# Pawn.net
KiCad netlist of a schematic drawn in EAGLE
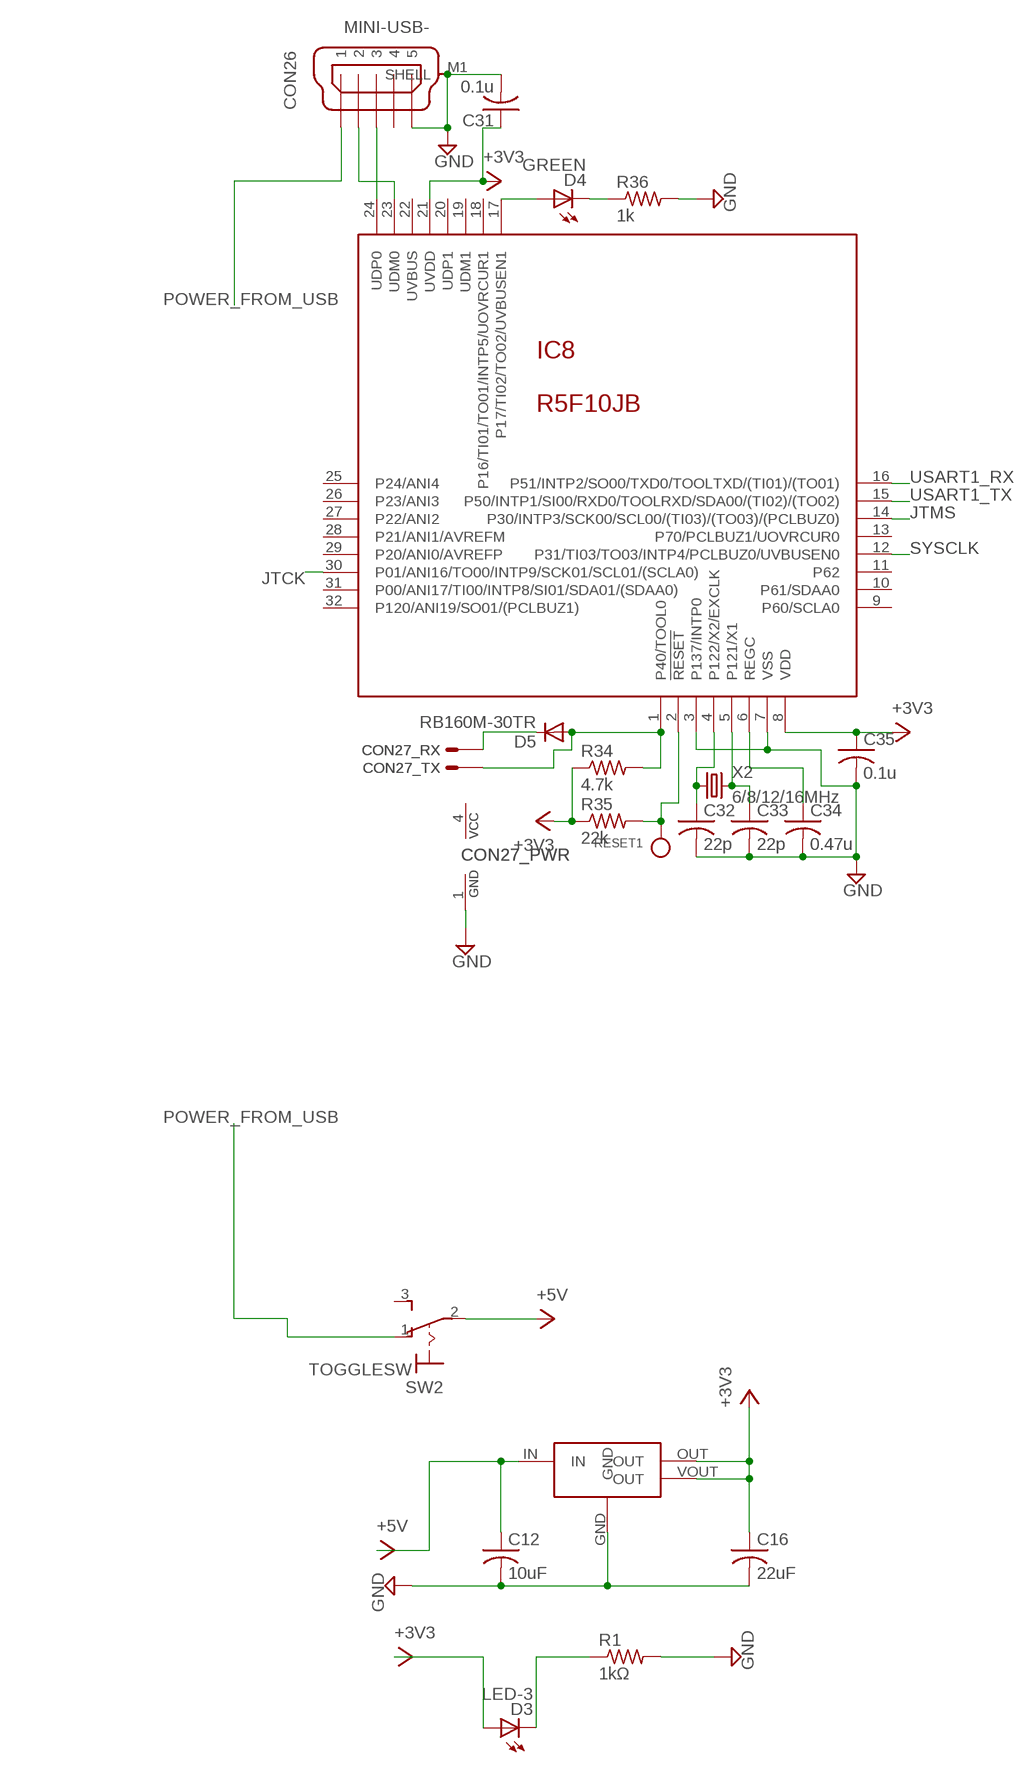
[diagram p0: schematic, sheet 1, part 1 of 2]
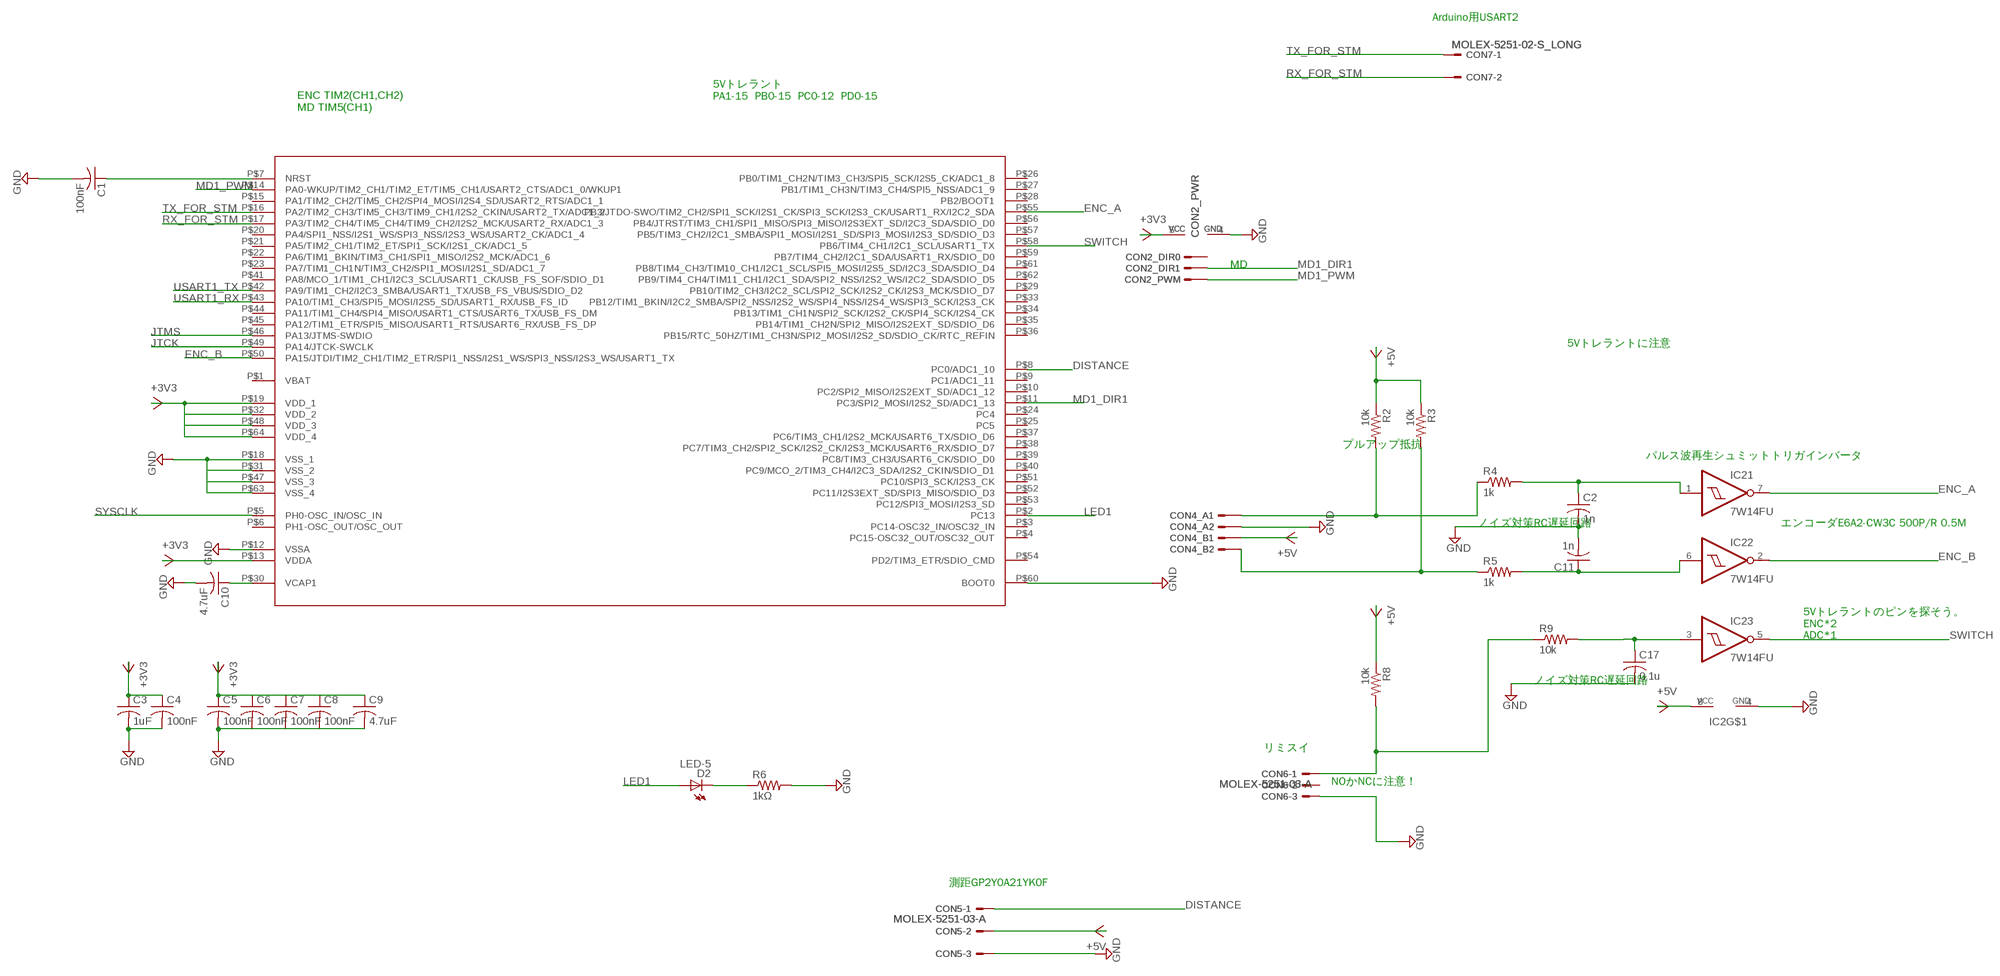
[diagram p1: schematic, sheet 1, part 2 of 2]

(export (version "E")
  (design (tool "Eeschema 10.0.6"))
  (components
    (comp (ref "C1")
      (value "100nF")
      (footprint "eagle-import:2012-C")
      (libsource (lib "eagle-import") (part "C-2012"))
    )
    (comp (ref "C2")
      (value "1n")
      (footprint "eagle-import:2012-C")
      (libsource (lib "eagle-import") (part "C-2012"))
    )
    (comp (ref "C3")
      (value "1uF")
      (footprint "eagle-import:2012-C")
      (libsource (lib "eagle-import") (part "C-2012"))
    )
    (comp (ref "C4")
      (value "100nF")
      (footprint "eagle-import:2012-C")
      (libsource (lib "eagle-import") (part "C-2012"))
    )
    (comp (ref "C5")
      (value "100nF")
      (footprint "eagle-import:2012-C")
      (libsource (lib "eagle-import") (part "C-2012"))
    )
    (comp (ref "C6")
      (value "100nF")
      (footprint "eagle-import:2012-C")
      (libsource (lib "eagle-import") (part "C-2012"))
    )
    (comp (ref "C7")
      (value "100nF")
      (footprint "eagle-import:2012-C")
      (libsource (lib "eagle-import") (part "C-2012"))
    )
    (comp (ref "C8")
      (value "100nF")
      (footprint "eagle-import:2012-C")
      (libsource (lib "eagle-import") (part "C-2012"))
    )
    (comp (ref "C9")
      (value "4.7uF")
      (footprint "eagle-import:2012-C")
      (libsource (lib "eagle-import") (part "C-2012"))
    )
    (comp (ref "C10")
      (value "4.7uF")
      (footprint "eagle-import:2012-C")
      (libsource (lib "eagle-import") (part "C-2012"))
    )
    (comp (ref "C11")
      (value "1n")
      (footprint "eagle-import:2012-C")
      (libsource (lib "eagle-import") (part "C-2012"))
    )
    (comp (ref "C12")
      (value "10uF")
      (footprint "eagle-import:2012-C")
      (libsource (lib "eagle-import") (part "C-2012"))
    )
    (comp (ref "C16")
      (value "22uF")
      (footprint "eagle-import:2012-C")
      (libsource (lib "eagle-import") (part "C-2012"))
    )
    (comp (ref "C17")
      (value "0.1u")
      (footprint "eagle-import:2012-C")
      (libsource (lib "eagle-import") (part "C-2012"))
    )
    (comp (ref "C31")
      (value "0.1u")
      (footprint "eagle-import:2012-C")
      (libsource (lib "eagle-import") (part "C-2012"))
    )
    (comp (ref "C32")
      (value "22p")
      (footprint "eagle-import:1608")
      (libsource (lib "eagle-import") (part "C-1608"))
    )
    (comp (ref "C33")
      (value "22p")
      (footprint "eagle-import:1608")
      (libsource (lib "eagle-import") (part "C-1608"))
    )
    (comp (ref "C34")
      (value "0.47u")
      (footprint "eagle-import:2012-C")
      (libsource (lib "eagle-import") (part "C-2012"))
    )
    (comp (ref "C35")
      (value "0.1u")
      (footprint "eagle-import:2012-C")
      (libsource (lib "eagle-import") (part "C-2012"))
    )
    (comp (ref "CON2")
      (value "MTDRV-A")
      (footprint "eagle-import:5251-05-A")
      (libsource (lib "eagle-import") (part "MTDRV-A"))
    )
    (comp (ref "CON4")
      (value "D-3500-4")
      (footprint "eagle-import:D3500D-4-HORIZONTAL")
      (libsource (lib "eagle-import") (part "D-3500-4"))
    )
    (comp (ref "CON5")
      (value "MOLEX-5251-03-A")
      (footprint "eagle-import:5251-03-A")
      (libsource (lib "eagle-import") (part "MOLEX-5251-03-A"))
    )
    (comp (ref "CON6")
      (value "MOLEX-5251-03-A")
      (footprint "eagle-import:5251-03-A")
      (libsource (lib "eagle-import") (part "MOLEX-5251-03-A"))
    )
    (comp (ref "CON7")
      (value "MOLEX-5251-02-S_LONG")
      (footprint "eagle-import:5251-02-S_LONG")
      (libsource (lib "eagle-import") (part "MOLEX-5251-02-S_LONG"))
    )
    (comp (ref "CON26")
      (value "MINI-USB-")
      (footprint "eagle-import:UX60A-MB-5ST")
      (libsource (lib "eagle-import") (part "MINI-USB-"))
    )
    (comp (ref "CON27")
      (value "UART-S")
      (footprint "eagle-import:IL-G-04-S")
      (libsource (lib "eagle-import") (part "UART-S"))
    )
    (comp (ref "D2")
      (value "LED-5")
      (footprint "eagle-import:LED5")
      (libsource (lib "eagle-import") (part "LED-5"))
    )
    (comp (ref "D3")
      (value "LED-3")
      (footprint "eagle-import:LED3")
      (libsource (lib "eagle-import") (part "LED-3"))
    )
    (comp (ref "D4")
      (value "GREEN")
      (footprint "eagle-import:LED3")
      (libsource (lib "eagle-import") (part "LED-3"))
    )
    (comp (ref "D5")
      (value "RB160M-30TR")
      (footprint "eagle-import:D3216")
      (libsource (lib "eagle-import") (part "DIODE-SMD3216"))
    )
    (comp (ref "IC1")
      (value "AZ1086H-3.3")
      (footprint "eagle-import:SOT223")
      (libsource (lib "eagle-import") (part "AZ1086?-H3.3"))
    )
    (comp (ref "IC2")
      (value "7W14FU")
      (footprint "eagle-import:MSOP8")
      (libsource (lib "eagle-import") (part "7W14FU"))
    )
    (comp (ref "IC8")
      (value "R5F10JB")
      (footprint "eagle-import:TQFP32-08")
      (libsource (lib "eagle-import") (part "R5F10JB"))
    )
    (comp (ref "R1")
      (value "1kΩ")
      (footprint "eagle-import:2012-R")
      (libsource (lib "eagle-import") (part "R-2012"))
    )
    (comp (ref "R2")
      (value "10k")
      (footprint "eagle-import:2012-R")
      (libsource (lib "eagle-import") (part "R-2012"))
    )
    (comp (ref "R3")
      (value "10k")
      (footprint "eagle-import:2012-R")
      (libsource (lib "eagle-import") (part "R-2012"))
    )
    (comp (ref "R4")
      (value "1k")
      (footprint "eagle-import:2012-R")
      (libsource (lib "eagle-import") (part "R-2012"))
    )
    (comp (ref "R5")
      (value "1k")
      (footprint "eagle-import:2012-R")
      (libsource (lib "eagle-import") (part "R-2012"))
    )
    (comp (ref "R6")
      (value "1kΩ")
      (footprint "eagle-import:2012-R")
      (libsource (lib "eagle-import") (part "R-2012"))
    )
    (comp (ref "R8")
      (value "10k")
      (footprint "eagle-import:2012-R")
      (libsource (lib "eagle-import") (part "R-2012"))
    )
    (comp (ref "R9")
      (value "10k")
      (footprint "eagle-import:2012-R")
      (libsource (lib "eagle-import") (part "R-2012"))
    )
    (comp (ref "R34")
      (value "4.7k")
      (footprint "eagle-import:2012-R")
      (libsource (lib "eagle-import") (part "R-2012"))
    )
    (comp (ref "R35")
      (value "22k")
      (footprint "eagle-import:2012-R")
      (libsource (lib "eagle-import") (part "R-2012"))
    )
    (comp (ref "R36")
      (value "1k")
      (footprint "eagle-import:2012-R")
      (libsource (lib "eagle-import") (part "R-2012"))
    )
    (comp (ref "RESET1")
      (value "CHECK_PIN")
      (footprint "eagle-import:SLC-22-G")
      (libsource (lib "eagle-import") (part "CHECK_PIN"))
    )
    (comp (ref "SW2")
      (value "TOGGLESW")
      (footprint "eagle-import:TOGGLESW")
      (libsource (lib "eagle-import") (part "TOGGLESW"))
    )
    (comp (ref "U$1")
      (value "STM32F411RET6")
      (footprint "eagle-import:ET-PCB-LQFP64")
      (libsource (lib "eagle-import") (part "STM32F411RET6"))
    )
    (comp (ref "X2")
      (value "6/8/12/16MHz")
      (footprint "eagle-import:HC49_S")
      (libsource (lib "eagle-import") (part "CRYSTALHC49S"))
    )
  )
  (nets
    (net (code "1") (name "+3V3") (class "Default")
      (node (ref "C16") (pin "1") (pinfunction "1_1") (pintype "passive"))
      (node (ref "C3") (pin "1") (pinfunction "1_1") (pintype "passive"))
      (node (ref "C31") (pin "1") (pinfunction "1_1") (pintype "passive"))
      (node (ref "C35") (pin "1") (pinfunction "1_1") (pintype "passive"))
      (node (ref "C4") (pin "1") (pinfunction "1_1") (pintype "passive"))
      (node (ref "C5") (pin "1") (pinfunction "1_1") (pintype "passive"))
      (node (ref "C6") (pin "1") (pinfunction "1_1") (pintype "passive"))
      (node (ref "C7") (pin "1") (pinfunction "1_1") (pintype "passive"))
      (node (ref "C8") (pin "1") (pinfunction "1_1") (pintype "passive"))
      (node (ref "C9") (pin "1") (pinfunction "1_1") (pintype "passive"))
      (node (ref "CON2") (pin "5") (pinfunction "VCC_5") (pintype "power_in"))
      (node (ref "D3") (pin "A") (pinfunction "A_A") (pintype "passive"))
      (node (ref "IC1") (pin "OUT") (pinfunction "OUT_OUT") (pintype "power_in"))
      (node (ref "IC1") (pin "VOUT") (pinfunction "OUT_VOUT") (pintype "power_in"))
      (node (ref "IC8") (pin "21") (pinfunction "UVDD_21") (pintype "bidirectional"))
      (node (ref "IC8") (pin "8") (pinfunction "VDD_8") (pintype "bidirectional"))
      (node (ref "R34") (pin "1") (pinfunction "1_1") (pintype "passive"))
      (node (ref "R35") (pin "1") (pinfunction "1_1") (pintype "passive"))
      (node (ref "U$1") (pin "P$13") (pinfunction "VDDA_P$13") (pintype "bidirectional"))
      (node (ref "U$1") (pin "P$19") (pinfunction "VDD_1_P$19") (pintype "bidirectional"))
      (node (ref "U$1") (pin "P$32") (pinfunction "VDD_2_P$32") (pintype "bidirectional"))
      (node (ref "U$1") (pin "P$48") (pinfunction "VDD_3_P$48") (pintype "bidirectional"))
      (node (ref "U$1") (pin "P$64") (pinfunction "VDD_4_P$64") (pintype "bidirectional"))
    )
    (net (code "2") (name "+5V") (class "Default")
      (node (ref "C12") (pin "1") (pinfunction "1_1") (pintype "passive"))
      (node (ref "CON4") (pin "B1") (pinfunction "S_B1") (pintype "passive"))
      (node (ref "CON5") (pin "2") (pinfunction "S_2") (pintype "passive"))
      (node (ref "IC1") (pin "IN") (pinfunction "IN_IN") (pintype "power_in"))
      (node (ref "IC2") (pin "8") (pinfunction "VCC_8") (pintype "power_in"))
      (node (ref "R2") (pin "1") (pinfunction "1_1") (pintype "passive"))
      (node (ref "R3") (pin "1") (pinfunction "1_1") (pintype "passive"))
      (node (ref "R8") (pin "1") (pinfunction "1_1") (pintype "passive"))
      (node (ref "SW2") (pin "2") (pinfunction "P_2") (pintype "passive"))
    )
    (net (code "3") (name "/DISTANCE") (class "Default")
      (node (ref "CON5") (pin "1") (pinfunction "S_1") (pintype "passive"))
      (node (ref "U$1") (pin "P$8") (pinfunction "PC0/ADC1_10_P$8") (pintype "bidirectional"))
    )
    (net (code "4") (name "/ENC_A") (class "Default")
      (node (ref "IC2") (pin "7") (pinfunction "Y_7") (pintype "output"))
      (node (ref "U$1") (pin "P$55") (pinfunction "PB3/JTDO-SWO/TIM2_CH2/SPI1_SCK/I2S1_CK/SPI3_SCK/I2S3_CK/USART1_RX/I2C2_SDA_P$55") (pintype "bidirectional"))
    )
    (net (code "5") (name "/ENC_B") (class "Default")
      (node (ref "IC2") (pin "2") (pinfunction "Y_2") (pintype "output"))
      (node (ref "U$1") (pin "P$50") (pinfunction "PA15/JTDI/TIM2_CH1/TIM2_ETR/SPI1_NSS/I2S1_WS/SPI3_NSS/I2S3_WS/USART1_TX_P$50") (pintype "bidirectional"))
    )
    (net (code "6") (name "/JTCK") (class "Default")
      (node (ref "IC8") (pin "30") (pinfunction "P01/ANI16/TO00/INTP9/SCK01/SCL01/(SCLA0)_30") (pintype "bidirectional"))
      (node (ref "U$1") (pin "P$49") (pinfunction "PA14/JTCK-SWCLK_P$49") (pintype "bidirectional"))
    )
    (net (code "7") (name "/JTMS") (class "Default")
      (node (ref "IC8") (pin "14") (pinfunction "P30/INTP3/SCK00/SCL00/(TI03)/(TO03)/(PCLBUZ0)_14") (pintype "bidirectional"))
      (node (ref "U$1") (pin "P$46") (pinfunction "PA13/JTMS-SWDIO_P$46") (pintype "bidirectional"))
    )
    (net (code "8") (name "/LED1") (class "Default")
      (node (ref "D2") (pin "A") (pinfunction "A_A") (pintype "passive"))
      (node (ref "U$1") (pin "P$2") (pinfunction "PC13_P$2") (pintype "bidirectional"))
    )
    (net (code "9") (name "/MD1_DIR1") (class "Default")
      (node (ref "CON2") (pin "2") (pinfunction "S_2") (pintype "passive"))
      (node (ref "U$1") (pin "P$11") (pinfunction "PC3/SPI2_MOSI/I2S2_SD/ADC1_13_P$11") (pintype "bidirectional"))
    )
    (net (code "10") (name "/MD1_PWM") (class "Default")
      (node (ref "CON2") (pin "1") (pinfunction "S_1") (pintype "passive"))
      (node (ref "U$1") (pin "P$14") (pinfunction "PA0-WKUP/TIM2_CH1/TIM2_ET/TIM5_CH1/USART2_CTS/ADC1_0/WKUP1_P$14") (pintype "bidirectional"))
    )
    (net (code "11") (name "/POWER_FROM_USB") (class "Default")
      (node (ref "CON26") (pin "1") (pinfunction "1_1") (pintype "input"))
      (node (ref "SW2") (pin "1") (pinfunction "O_1") (pintype "passive"))
    )
    (net (code "12") (name "/RX_FOR_STM") (class "Default")
      (node (ref "CON7") (pin "2") (pinfunction "S_2") (pintype "passive"))
      (node (ref "U$1") (pin "P$17") (pinfunction "PA3/TIM2_CH4/TIM5_CH4/TIM9_CH2/I2S2_MCK/USART2_RX/ADC1_3_P$17") (pintype "bidirectional"))
    )
    (net (code "13") (name "/SWITCH") (class "Default")
      (node (ref "IC2") (pin "5") (pinfunction "Y_5") (pintype "output"))
      (node (ref "U$1") (pin "P$58") (pinfunction "PB6/TIM4_CH1/I2C1_SCL/USART1_TX_P$58") (pintype "bidirectional"))
    )
    (net (code "14") (name "/SYSCLK") (class "Default")
      (node (ref "IC8") (pin "12") (pinfunction "P31/TI03/TO03/INTP4/PCLBUZ0/UVBUSEN0_12") (pintype "bidirectional"))
      (node (ref "U$1") (pin "P$5") (pinfunction "PH0-OSC_IN/OSC_IN_P$5") (pintype "bidirectional"))
    )
    (net (code "15") (name "/TX_FOR_STM") (class "Default")
      (node (ref "CON7") (pin "1") (pinfunction "S_1") (pintype "passive"))
      (node (ref "U$1") (pin "P$16") (pinfunction "PA2/TIM2_CH3/TIM5_CH3/TIM9_CH1/I2S2_CKIN/USART2_TX/ADC1_2_P$16") (pintype "bidirectional"))
    )
    (net (code "16") (name "/USART1_RX") (class "Default")
      (node (ref "IC8") (pin "16") (pinfunction "P51/INTP2/SO00/TXD0/TOOLTXD/(TI01)/(TO01)_16") (pintype "bidirectional"))
      (node (ref "U$1") (pin "P$43") (pinfunction "PA10/TIM1_CH3/SPI5_MOSI/I2S5_SD/USART1_RX/USB_FS_ID_P$43") (pintype "bidirectional"))
    )
    (net (code "17") (name "/USART1_TX") (class "Default")
      (node (ref "IC8") (pin "15") (pinfunction "P50/INTP1/SI00/RXD0/TOOLRXD/SDA00/(TI02)/(TO02)_15") (pintype "bidirectional"))
      (node (ref "U$1") (pin "P$42") (pinfunction "PA9/TIM1_CH2/I2C3_SMBA/USART1_TX/USB_FS_VBUS/SDIO_D2_P$42") (pintype "bidirectional"))
    )
    (net (code "18") (name "/VCC") (class "Default")
      (node (ref "CON27") (pin "4") (pinfunction "VCC_4") (pintype "power_in"))
    )
    (net (code "19") (name "GND") (class "Default")
      (node (ref "C1") (pin "2") (pinfunction "2_2") (pintype "passive"))
      (node (ref "C10") (pin "2") (pinfunction "2_2") (pintype "passive"))
      (node (ref "C11") (pin "2") (pinfunction "2_2") (pintype "passive"))
      (node (ref "C12") (pin "2") (pinfunction "2_2") (pintype "passive"))
      (node (ref "C16") (pin "2") (pinfunction "2_2") (pintype "passive"))
      (node (ref "C17") (pin "2") (pinfunction "2_2") (pintype "passive"))
      (node (ref "C2") (pin "2") (pinfunction "2_2") (pintype "passive"))
      (node (ref "C3") (pin "2") (pinfunction "2_2") (pintype "passive"))
      (node (ref "C31") (pin "2") (pinfunction "2_2") (pintype "passive"))
      (node (ref "C32") (pin "2") (pinfunction "2_2") (pintype "passive"))
      (node (ref "C33") (pin "2") (pinfunction "2_2") (pintype "passive"))
      (node (ref "C34") (pin "2") (pinfunction "2_2") (pintype "passive"))
      (node (ref "C35") (pin "2") (pinfunction "2_2") (pintype "passive"))
      (node (ref "C4") (pin "2") (pinfunction "2_2") (pintype "passive"))
      (node (ref "C5") (pin "2") (pinfunction "2_2") (pintype "passive"))
      (node (ref "C6") (pin "2") (pinfunction "2_2") (pintype "passive"))
      (node (ref "C7") (pin "2") (pinfunction "2_2") (pintype "passive"))
      (node (ref "C8") (pin "2") (pinfunction "2_2") (pintype "passive"))
      (node (ref "C9") (pin "2") (pinfunction "2_2") (pintype "passive"))
      (node (ref "CON2") (pin "4") (pinfunction "GND_4") (pintype "power_in"))
      (node (ref "CON26") (pin "5") (pinfunction "5_5") (pintype "input"))
      (node (ref "CON26") (pin "M1") (pinfunction "SHELL_M1") (pintype "bidirectional"))
      (node (ref "CON27") (pin "1") (pinfunction "GND_1") (pintype "power_in"))
      (node (ref "CON4") (pin "A2") (pinfunction "S_A2") (pintype "passive"))
      (node (ref "CON5") (pin "3") (pinfunction "S_3") (pintype "passive"))
      (node (ref "CON6") (pin "3") (pinfunction "S_3") (pintype "passive"))
      (node (ref "IC1") (pin "GND") (pinfunction "GND_GND") (pintype "power_in"))
      (node (ref "IC2") (pin "4") (pinfunction "GND_4") (pintype "power_in"))
      (node (ref "IC8") (pin "3") (pinfunction "P137/INTP0_3") (pintype "bidirectional"))
      (node (ref "IC8") (pin "7") (pinfunction "VSS_7") (pintype "bidirectional"))
      (node (ref "R1") (pin "2") (pinfunction "2_2") (pintype "passive"))
      (node (ref "R36") (pin "2") (pinfunction "2_2") (pintype "passive"))
      (node (ref "R6") (pin "2") (pinfunction "2_2") (pintype "passive"))
      (node (ref "U$1") (pin "P$12") (pinfunction "VSSA_P$12") (pintype "bidirectional"))
      (node (ref "U$1") (pin "P$18") (pinfunction "VSS_1_P$18") (pintype "bidirectional"))
      (node (ref "U$1") (pin "P$31") (pinfunction "VSS_2_P$31") (pintype "bidirectional"))
      (node (ref "U$1") (pin "P$47") (pinfunction "VSS_3_P$47") (pintype "bidirectional"))
      (node (ref "U$1") (pin "P$60") (pinfunction "BOOT0_P$60") (pintype "bidirectional"))
      (node (ref "U$1") (pin "P$63") (pinfunction "VSS_4_P$63") (pintype "bidirectional"))
    )
    (net (code "20") (name "Net-(CON4A-S)") (class "Default")
      (node (ref "CON4") (pin "A1") (pinfunction "S_A1") (pintype "passive"))
      (node (ref "R2") (pin "2") (pinfunction "2_2") (pintype "passive"))
      (node (ref "R4") (pin "1") (pinfunction "1_1") (pintype "passive"))
    )
    (net (code "21") (name "Net-(CON4D-S)") (class "Default")
      (node (ref "CON4") (pin "B2") (pinfunction "S_B2") (pintype "passive"))
      (node (ref "R3") (pin "2") (pinfunction "2_2") (pintype "passive"))
      (node (ref "R5") (pin "1") (pinfunction "1_1") (pintype "passive"))
    )
    (net (code "22") (name "Net-(CON6A-S)") (class "Default")
      (node (ref "CON6") (pin "1") (pinfunction "S_1") (pintype "passive"))
      (node (ref "R8") (pin "2") (pinfunction "2_2") (pintype "passive"))
      (node (ref "R9") (pin "1") (pinfunction "1_1") (pintype "passive"))
    )
    (net (code "23") (name "Net-(CON27B-S)") (class "Default")
      (node (ref "CON27") (pin "2") (pinfunction "S_2") (pintype "passive"))
      (node (ref "D5") (pin "K") (pinfunction "C_K") (pintype "passive"))
    )
    (net (code "24") (name "Net-(CON27C-S)") (class "Default")
      (node (ref "CON27") (pin "3") (pinfunction "S_3") (pintype "passive"))
      (node (ref "D5") (pin "A") (pinfunction "A_A") (pintype "passive"))
      (node (ref "IC8") (pin "1") (pinfunction "P40/TOOL0_1") (pintype "bidirectional"))
      (node (ref "R34") (pin "2") (pinfunction "2_2") (pintype "passive"))
    )
    (net (code "25") (name "Net-(D2-PadK)") (class "Default")
      (node (ref "D2") (pin "K") (pinfunction "K_K") (pintype "passive"))
      (node (ref "R6") (pin "1") (pinfunction "1_1") (pintype "passive"))
    )
    (net (code "26") (name "Net-(D3-PadK)") (class "Default")
      (node (ref "D3") (pin "K") (pinfunction "K_K") (pintype "passive"))
      (node (ref "R1") (pin "1") (pinfunction "1_1") (pintype "passive"))
    )
    (net (code "27") (name "Net-(D4-PadK)") (class "Default")
      (node (ref "D4") (pin "K") (pinfunction "K_K") (pintype "passive"))
      (node (ref "R36") (pin "1") (pinfunction "1_1") (pintype "passive"))
    )
    (net (code "28") (name "Net-(IC2A-A)") (class "Default")
      (node (ref "C2") (pin "1") (pinfunction "1_1") (pintype "passive"))
      (node (ref "IC2") (pin "1") (pinfunction "A_1") (pintype "input"))
      (node (ref "R4") (pin "2") (pinfunction "2_2") (pintype "passive"))
    )
    (net (code "29") (name "Net-(IC2B-A)") (class "Default")
      (node (ref "C11") (pin "1") (pinfunction "1_1") (pintype "passive"))
      (node (ref "IC2") (pin "6") (pinfunction "A_6") (pintype "input"))
      (node (ref "R5") (pin "2") (pinfunction "2_2") (pintype "passive"))
    )
    (net (code "30") (name "Net-(IC2C-A)") (class "Default")
      (node (ref "C17") (pin "1") (pinfunction "1_1") (pintype "passive"))
      (node (ref "IC2") (pin "3") (pinfunction "A_3") (pintype "input"))
      (node (ref "R9") (pin "2") (pinfunction "2_2") (pintype "passive"))
    )
    (net (code "31") (name "Net-(IC8-P17{slash}TI02{slash}TO02{slash}UVBUSEN1)") (class "Default")
      (node (ref "D4") (pin "A") (pinfunction "A_A") (pintype "passive"))
      (node (ref "IC8") (pin "17") (pinfunction "P17/TI02/TO02/UVBUSEN1_17") (pintype "bidirectional"))
    )
    (net (code "32") (name "Net-(IC8-P121{slash}X1)") (class "Default")
      (node (ref "C33") (pin "1") (pinfunction "1_1") (pintype "passive"))
      (node (ref "IC8") (pin "5") (pinfunction "P121/X1_5") (pintype "bidirectional"))
      (node (ref "X2") (pin "2") (pinfunction "2_2") (pintype "passive"))
    )
    (net (code "33") (name "Net-(IC8-P122{slash}X2{slash}EXCLK)") (class "Default")
      (node (ref "C32") (pin "1") (pinfunction "1_1") (pintype "passive"))
      (node (ref "IC8") (pin "4") (pinfunction "P122/X2/EXCLK_4") (pintype "bidirectional"))
      (node (ref "X2") (pin "1") (pinfunction "1_1") (pintype "passive"))
    )
    (net (code "34") (name "Net-(IC8-REGC)") (class "Default")
      (node (ref "C34") (pin "1") (pinfunction "1_1") (pintype "passive"))
      (node (ref "IC8") (pin "6") (pinfunction "REGC_6") (pintype "bidirectional"))
    )
    (net (code "35") (name "Net-(IC8-UDM0)") (class "Default")
      (node (ref "CON26") (pin "2") (pinfunction "2_2") (pintype "input"))
      (node (ref "IC8") (pin "23") (pinfunction "UDM0_23") (pintype "bidirectional"))
    )
    (net (code "36") (name "Net-(IC8-UDP0)") (class "Default")
      (node (ref "CON26") (pin "3") (pinfunction "3_3") (pintype "input"))
      (node (ref "IC8") (pin "24") (pinfunction "UDP0_24") (pintype "bidirectional"))
    )
    (net (code "37") (name "Net-(IC8-~{RESET})") (class "Default")
      (node (ref "IC8") (pin "2") (pinfunction "~{RESET}_2") (pintype "bidirectional"))
      (node (ref "R35") (pin "2") (pinfunction "2_2") (pintype "passive"))
      (node (ref "RESET1") (pin "SIGNAL") (pinfunction "SIGNAL_SIGNAL") (pintype "bidirectional"))
    )
    (net (code "38") (name "Net-(U$1-NRST)") (class "Default")
      (node (ref "C1") (pin "1") (pinfunction "1_1") (pintype "passive"))
      (node (ref "U$1") (pin "P$7") (pinfunction "NRST_P$7") (pintype "bidirectional"))
    )
    (net (code "39") (name "Net-(U$1-VCAP1)") (class "Default")
      (node (ref "C10") (pin "1") (pinfunction "1_1") (pintype "passive"))
      (node (ref "U$1") (pin "P$30") (pinfunction "VCAP1_P$30") (pintype "bidirectional"))
    )
    (net (code "40") (name "unconnected-(CON2A-S-Pad3)") (class "Default")
      (node (ref "CON2") (pin "3") (pinfunction "S_3") (pintype "passive"))
    )
    (net (code "41") (name "unconnected-(CON6B-S-Pad2)") (class "Default")
      (node (ref "CON6") (pin "2") (pinfunction "S_2") (pintype "passive"))
    )
    (net (code "42") (name "unconnected-(CON26-Pad4)") (class "Default")
      (node (ref "CON26") (pin "4") (pinfunction "4_4") (pintype "input"))
    )
    (net (code "43") (name "unconnected-(IC8-P00{slash}ANI17{slash}TI00{slash}INTP8{slash}SI01{slash}SDA01{slash}(SDAA0)-Pad31)") (class "Default")
      (node (ref "IC8") (pin "31") (pinfunction "P00/ANI17/TI00/INTP8/SI01/SDA01/(SDAA0)_31") (pintype "bidirectional"))
    )
    (net (code "44") (name "unconnected-(IC8-P16{slash}TI01{slash}TO01{slash}INTP5{slash}UOVRCUR1-Pad18)") (class "Default")
      (node (ref "IC8") (pin "18") (pinfunction "P16/TI01/TO01/INTP5/UOVRCUR1_18") (pintype "bidirectional"))
    )
    (net (code "45") (name "unconnected-(IC8-P20{slash}ANI0{slash}AVREFP-Pad29)") (class "Default")
      (node (ref "IC8") (pin "29") (pinfunction "P20/ANI0/AVREFP_29") (pintype "bidirectional"))
    )
    (net (code "46") (name "unconnected-(IC8-P21{slash}ANI1{slash}AVREFM-Pad28)") (class "Default")
      (node (ref "IC8") (pin "28") (pinfunction "P21/ANI1/AVREFM_28") (pintype "bidirectional"))
    )
    (net (code "47") (name "unconnected-(IC8-P22{slash}ANI2-Pad27)") (class "Default")
      (node (ref "IC8") (pin "27") (pinfunction "P22/ANI2_27") (pintype "bidirectional"))
    )
    (net (code "48") (name "unconnected-(IC8-P23{slash}ANI3-Pad26)") (class "Default")
      (node (ref "IC8") (pin "26") (pinfunction "P23/ANI3_26") (pintype "bidirectional"))
    )
    (net (code "49") (name "unconnected-(IC8-P24{slash}ANI4-Pad25)") (class "Default")
      (node (ref "IC8") (pin "25") (pinfunction "P24/ANI4_25") (pintype "bidirectional"))
    )
    (net (code "50") (name "unconnected-(IC8-P60{slash}SCLA0-Pad9)") (class "Default")
      (node (ref "IC8") (pin "9") (pinfunction "P60/SCLA0_9") (pintype "bidirectional"))
    )
    (net (code "51") (name "unconnected-(IC8-P61{slash}SDAA0-Pad10)") (class "Default")
      (node (ref "IC8") (pin "10") (pinfunction "P61/SDAA0_10") (pintype "bidirectional"))
    )
    (net (code "52") (name "unconnected-(IC8-P62-Pad11)") (class "Default")
      (node (ref "IC8") (pin "11") (pinfunction "P62_11") (pintype "bidirectional"))
    )
    (net (code "53") (name "unconnected-(IC8-P70{slash}PCLBUZ1{slash}UOVRCUR0-Pad13)") (class "Default")
      (node (ref "IC8") (pin "13") (pinfunction "P70/PCLBUZ1/UOVRCUR0_13") (pintype "bidirectional"))
    )
    (net (code "54") (name "unconnected-(IC8-P120{slash}ANI19{slash}SO01{slash}(PCLBUZ1)-Pad32)") (class "Default")
      (node (ref "IC8") (pin "32") (pinfunction "P120/ANI19/SO01/(PCLBUZ1)_32") (pintype "bidirectional"))
    )
    (net (code "55") (name "unconnected-(IC8-UDM1-Pad19)") (class "Default")
      (node (ref "IC8") (pin "19") (pinfunction "UDM1_19") (pintype "bidirectional"))
    )
    (net (code "56") (name "unconnected-(IC8-UDP1-Pad20)") (class "Default")
      (node (ref "IC8") (pin "20") (pinfunction "UDP1_20") (pintype "bidirectional"))
    )
    (net (code "57") (name "unconnected-(IC8-UVBUS-Pad22)") (class "Default")
      (node (ref "IC8") (pin "22") (pinfunction "UVBUS_22") (pintype "bidirectional"))
    )
    (net (code "58") (name "unconnected-(SW2A-S-Pad3)") (class "Default")
      (node (ref "SW2") (pin "3") (pinfunction "S_3") (pintype "passive"))
    )
    (net (code "59") (name "unconnected-(U$1-PA1{slash}TIM2_CH2{slash}TIM5_CH2{slash}SPI4_MOSI{slash}I2S4_SD{slash}USART2_RTS{slash}ADC1_1-PadP$15)") (class "Default")
      (node (ref "U$1") (pin "P$15") (pinfunction "PA1/TIM2_CH2/TIM5_CH2/SPI4_MOSI/I2S4_SD/USART2_RTS/ADC1_1_P$15") (pintype "bidirectional"))
    )
    (net (code "60") (name "unconnected-(U$1-PA4{slash}SPI1_NSS{slash}I2S1_WS{slash}SPI3_NSS{slash}I2S3_WS{slash}USART2_CK{slash}ADC1_4-PadP$20)") (class "Default")
      (node (ref "U$1") (pin "P$20") (pinfunction "PA4/SPI1_NSS/I2S1_WS/SPI3_NSS/I2S3_WS/USART2_CK/ADC1_4_P$20") (pintype "bidirectional"))
    )
    (net (code "61") (name "unconnected-(U$1-PA5{slash}TIM2_CH1{slash}TIM2_ET{slash}SPI1_SCK{slash}I2S1_CK{slash}ADC1_5-PadP$21)") (class "Default")
      (node (ref "U$1") (pin "P$21") (pinfunction "PA5/TIM2_CH1/TIM2_ET/SPI1_SCK/I2S1_CK/ADC1_5_P$21") (pintype "bidirectional"))
    )
    (net (code "62") (name "unconnected-(U$1-PA6{slash}TIM1_BKIN{slash}TIM3_CH1{slash}SPI1_MISO{slash}I2S2_MCK{slash}ADC1_6-PadP$22)") (class "Default")
      (node (ref "U$1") (pin "P$22") (pinfunction "PA6/TIM1_BKIN/TIM3_CH1/SPI1_MISO/I2S2_MCK/ADC1_6_P$22") (pintype "bidirectional"))
    )
    (net (code "63") (name "unconnected-(U$1-PA7{slash}TIM1_CH1N{slash}TIM3_CH2{slash}SPI1_MOSI{slash}I2S1_SD{slash}ADC1_7-PadP$23)") (class "Default")
      (node (ref "U$1") (pin "P$23") (pinfunction "PA7/TIM1_CH1N/TIM3_CH2/SPI1_MOSI/I2S1_SD/ADC1_7_P$23") (pintype "bidirectional"))
    )
    (net (code "64") (name "unconnected-(U$1-PA8{slash}MCO_1{slash}TIM1_CH1{slash}I2C3_SCL{slash}USART1_CK{slash}USB_FS_SOF{slash}SDIO_D1-PadP$41)") (class "Default")
      (node (ref "U$1") (pin "P$41") (pinfunction "PA8/MCO_1/TIM1_CH1/I2C3_SCL/USART1_CK/USB_FS_SOF/SDIO_D1_P$41") (pintype "bidirectional"))
    )
    (net (code "65") (name "unconnected-(U$1-PA11{slash}TIM1_CH4{slash}SPI4_MISO{slash}USART1_CTS{slash}USART6_TX{slash}USB_FS_DM-PadP$44)") (class "Default")
      (node (ref "U$1") (pin "P$44") (pinfunction "PA11/TIM1_CH4/SPI4_MISO/USART1_CTS/USART6_TX/USB_FS_DM_P$44") (pintype "bidirectional"))
    )
    (net (code "66") (name "unconnected-(U$1-PA12{slash}TIM1_ETR{slash}SPI5_MISO{slash}USART1_RTS{slash}USART6_RX{slash}USB_FS_DP-PadP$45)") (class "Default")
      (node (ref "U$1") (pin "P$45") (pinfunction "PA12/TIM1_ETR/SPI5_MISO/USART1_RTS/USART6_RX/USB_FS_DP_P$45") (pintype "bidirectional"))
    )
    (net (code "67") (name "unconnected-(U$1-PB0{slash}TIM1_CH2N{slash}TIM3_CH3{slash}SPI5_SCK{slash}I2S5_CK{slash}ADC1_8-PadP$26)") (class "Default")
      (node (ref "U$1") (pin "P$26") (pinfunction "PB0/TIM1_CH2N/TIM3_CH3/SPI5_SCK/I2S5_CK/ADC1_8_P$26") (pintype "bidirectional"))
    )
    (net (code "68") (name "unconnected-(U$1-PB1{slash}TIM1_CH3N{slash}TIM3_CH4{slash}SPI5_NSS{slash}ADC1_9-PadP$27)") (class "Default")
      (node (ref "U$1") (pin "P$27") (pinfunction "PB1/TIM1_CH3N/TIM3_CH4/SPI5_NSS/ADC1_9_P$27") (pintype "bidirectional"))
    )
    (net (code "69") (name "unconnected-(U$1-PB2{slash}BOOT1-PadP$28)") (class "Default")
      (node (ref "U$1") (pin "P$28") (pinfunction "PB2/BOOT1_P$28") (pintype "bidirectional"))
    )
    (net (code "70") (name "unconnected-(U$1-PB4{slash}JTRST{slash}TIM3_CH1{slash}SPI1_MISO{slash}SPI3_MISO{slash}I2S3EXT_SD{slash}I2C3_SDA{slash}SDIO_D0-PadP$56)") (class "Default")
      (node (ref "U$1") (pin "P$56") (pinfunction "PB4/JTRST/TIM3_CH1/SPI1_MISO/SPI3_MISO/I2S3EXT_SD/I2C3_SDA/SDIO_D0_P$56") (pintype "bidirectional"))
    )
    (net (code "71") (name "unconnected-(U$1-PB5{slash}TIM3_CH2{slash}I2C1_SMBA{slash}SPI1_MOSI{slash}I2S1_SD{slash}SPI3_MOSI{slash}I2S3_SD{slash}SDIO_D3-PadP$57)") (class "Default")
      (node (ref "U$1") (pin "P$57") (pinfunction "PB5/TIM3_CH2/I2C1_SMBA/SPI1_MOSI/I2S1_SD/SPI3_MOSI/I2S3_SD/SDIO_D3_P$57") (pintype "bidirectional"))
    )
    (net (code "72") (name "unconnected-(U$1-PB7{slash}TIM4_CH2{slash}I2C1_SDA{slash}USART1_RX{slash}SDIO_D0-PadP$59)") (class "Default")
      (node (ref "U$1") (pin "P$59") (pinfunction "PB7/TIM4_CH2/I2C1_SDA/USART1_RX/SDIO_D0_P$59") (pintype "bidirectional"))
    )
    (net (code "73") (name "unconnected-(U$1-PB8{slash}TIM4_CH3{slash}TIM10_CH1{slash}I2C1_SCL{slash}SPI5_MOSI{slash}I2S5_SD{slash}I2C3_SDA{slash}SDIO_D4-PadP$61)") (class "Default")
      (node (ref "U$1") (pin "P$61") (pinfunction "PB8/TIM4_CH3/TIM10_CH1/I2C1_SCL/SPI5_MOSI/I2S5_SD/I2C3_SDA/SDIO_D4_P$61") (pintype "bidirectional"))
    )
    (net (code "74") (name "unconnected-(U$1-PB9{slash}TIM4_CH4{slash}TIM11_CH1{slash}I2C1_SDA{slash}SPI2_NSS{slash}I2S2_WS{slash}I2C2_SDA{slash}SDIO_D5-PadP$62)") (class "Default")
      (node (ref "U$1") (pin "P$62") (pinfunction "PB9/TIM4_CH4/TIM11_CH1/I2C1_SDA/SPI2_NSS/I2S2_WS/I2C2_SDA/SDIO_D5_P$62") (pintype "bidirectional"))
    )
    (net (code "75") (name "unconnected-(U$1-PB10{slash}TIM2_CH3{slash}I2C2_SCL{slash}SPI2_SCK{slash}I2S2_CK{slash}I2S3_MCK{slash}SDIO_D7-PadP$29)") (class "Default")
      (node (ref "U$1") (pin "P$29") (pinfunction "PB10/TIM2_CH3/I2C2_SCL/SPI2_SCK/I2S2_CK/I2S3_MCK/SDIO_D7_P$29") (pintype "bidirectional"))
    )
    (net (code "76") (name "unconnected-(U$1-PB12{slash}TIM1_BKIN{slash}I2C2_SMBA{slash}SPI2_NSS{slash}I2S2_WS{slash}SPI4_NSS{slash}I2S4_WS{slash}SPI3_SCK{slash}I2S3_CK-PadP$33)") (class "Default")
      (node (ref "U$1") (pin "P$33") (pinfunction "PB12/TIM1_BKIN/I2C2_SMBA/SPI2_NSS/I2S2_WS/SPI4_NSS/I2S4_WS/SPI3_SCK/I2S3_CK_P$33") (pintype "bidirectional"))
    )
    (net (code "77") (name "unconnected-(U$1-PB13{slash}TIM1_CH1N{slash}SPI2_SCK{slash}I2S2_CK{slash}SPI4_SCK{slash}I2S4_CK-PadP$34)") (class "Default")
      (node (ref "U$1") (pin "P$34") (pinfunction "PB13/TIM1_CH1N/SPI2_SCK/I2S2_CK/SPI4_SCK/I2S4_CK_P$34") (pintype "bidirectional"))
    )
    (net (code "78") (name "unconnected-(U$1-PB14{slash}TIM1_CH2N{slash}SPI2_MISO{slash}I2S2EXT_SD{slash}SDIO_D6-PadP$35)") (class "Default")
      (node (ref "U$1") (pin "P$35") (pinfunction "PB14/TIM1_CH2N/SPI2_MISO/I2S2EXT_SD/SDIO_D6_P$35") (pintype "bidirectional"))
    )
    (net (code "79") (name "unconnected-(U$1-PB15{slash}RTC_50HZ{slash}TIM1_CH3N{slash}SPI2_MOSI{slash}I2S2_SD{slash}SDIO_CK{slash}RTC_REFIN-PadP$36)") (class "Default")
      (node (ref "U$1") (pin "P$36") (pinfunction "PB15/RTC_50HZ/TIM1_CH3N/SPI2_MOSI/I2S2_SD/SDIO_CK/RTC_REFIN_P$36") (pintype "bidirectional"))
    )
    (net (code "80") (name "unconnected-(U$1-PC1{slash}ADC1_11-PadP$9)") (class "Default")
      (node (ref "U$1") (pin "P$9") (pinfunction "PC1/ADC1_11_P$9") (pintype "bidirectional"))
    )
    (net (code "81") (name "unconnected-(U$1-PC2{slash}SPI2_MISO{slash}I2S2EXT_SD{slash}ADC1_12-PadP$10)") (class "Default")
      (node (ref "U$1") (pin "P$10") (pinfunction "PC2/SPI2_MISO/I2S2EXT_SD/ADC1_12_P$10") (pintype "bidirectional"))
    )
    (net (code "82") (name "unconnected-(U$1-PC4-PadP$24)") (class "Default")
      (node (ref "U$1") (pin "P$24") (pinfunction "PC4_P$24") (pintype "bidirectional"))
    )
    (net (code "83") (name "unconnected-(U$1-PC5-PadP$25)") (class "Default")
      (node (ref "U$1") (pin "P$25") (pinfunction "PC5_P$25") (pintype "bidirectional"))
    )
    (net (code "84") (name "unconnected-(U$1-PC6{slash}TIM3_CH1{slash}I2S2_MCK{slash}USART6_TX{slash}SDIO_D6-PadP$37)") (class "Default")
      (node (ref "U$1") (pin "P$37") (pinfunction "PC6/TIM3_CH1/I2S2_MCK/USART6_TX/SDIO_D6_P$37") (pintype "bidirectional"))
    )
    (net (code "85") (name "unconnected-(U$1-PC7{slash}TIM3_CH2{slash}SPI2_SCK{slash}I2S2_CK{slash}I2S3_MCK{slash}USART6_RX{slash}SDIO_D7-PadP$38)") (class "Default")
      (node (ref "U$1") (pin "P$38") (pinfunction "PC7/TIM3_CH2/SPI2_SCK/I2S2_CK/I2S3_MCK/USART6_RX/SDIO_D7_P$38") (pintype "bidirectional"))
    )
    (net (code "86") (name "unconnected-(U$1-PC8{slash}TIM3_CH3{slash}USART6_CK{slash}SDIO_D0-PadP$39)") (class "Default")
      (node (ref "U$1") (pin "P$39") (pinfunction "PC8/TIM3_CH3/USART6_CK/SDIO_D0_P$39") (pintype "bidirectional"))
    )
    (net (code "87") (name "unconnected-(U$1-PC9{slash}MCO_2{slash}TIM3_CH4{slash}I2C3_SDA{slash}I2S2_CKIN{slash}SDIO_D1-PadP$40)") (class "Default")
      (node (ref "U$1") (pin "P$40") (pinfunction "PC9/MCO_2/TIM3_CH4/I2C3_SDA/I2S2_CKIN/SDIO_D1_P$40") (pintype "bidirectional"))
    )
    (net (code "88") (name "unconnected-(U$1-PC10{slash}SPI3_SCK{slash}I2S3_CK-PadP$51)") (class "Default")
      (node (ref "U$1") (pin "P$51") (pinfunction "PC10/SPI3_SCK/I2S3_CK_P$51") (pintype "bidirectional"))
    )
    (net (code "89") (name "unconnected-(U$1-PC11{slash}I2S3EXT_SD{slash}SPI3_MISO{slash}SDIO_D3-PadP$52)") (class "Default")
      (node (ref "U$1") (pin "P$52") (pinfunction "PC11/I2S3EXT_SD/SPI3_MISO/SDIO_D3_P$52") (pintype "bidirectional"))
    )
    (net (code "90") (name "unconnected-(U$1-PC12{slash}SPI3_MOSI{slash}I2S3_SD-PadP$53)") (class "Default")
      (node (ref "U$1") (pin "P$53") (pinfunction "PC12/SPI3_MOSI/I2S3_SD_P$53") (pintype "bidirectional"))
    )
    (net (code "91") (name "unconnected-(U$1-PC14-OSC32_IN{slash}OSC32_IN-PadP$3)") (class "Default")
      (node (ref "U$1") (pin "P$3") (pinfunction "PC14-OSC32_IN/OSC32_IN_P$3") (pintype "bidirectional"))
    )
    (net (code "92") (name "unconnected-(U$1-PC15-OSC32_OUT{slash}OSC32_OUT-PadP$4)") (class "Default")
      (node (ref "U$1") (pin "P$4") (pinfunction "PC15-OSC32_OUT/OSC32_OUT_P$4") (pintype "bidirectional"))
    )
    (net (code "93") (name "unconnected-(U$1-PD2{slash}TIM3_ETR{slash}SDIO_CMD-PadP$54)") (class "Default")
      (node (ref "U$1") (pin "P$54") (pinfunction "PD2/TIM3_ETR/SDIO_CMD_P$54") (pintype "bidirectional"))
    )
    (net (code "94") (name "unconnected-(U$1-PH1-OSC_OUT{slash}OSC_OUT-PadP$6)") (class "Default")
      (node (ref "U$1") (pin "P$6") (pinfunction "PH1-OSC_OUT/OSC_OUT_P$6") (pintype "bidirectional"))
    )
    (net (code "95") (name "unconnected-(U$1-VBAT-PadP$1)") (class "Default")
      (node (ref "U$1") (pin "P$1") (pinfunction "VBAT_P$1") (pintype "bidirectional"))
    )
  )
)
